# Dashboard.net
KiCad netlist of a schematic drawn in EAGLE
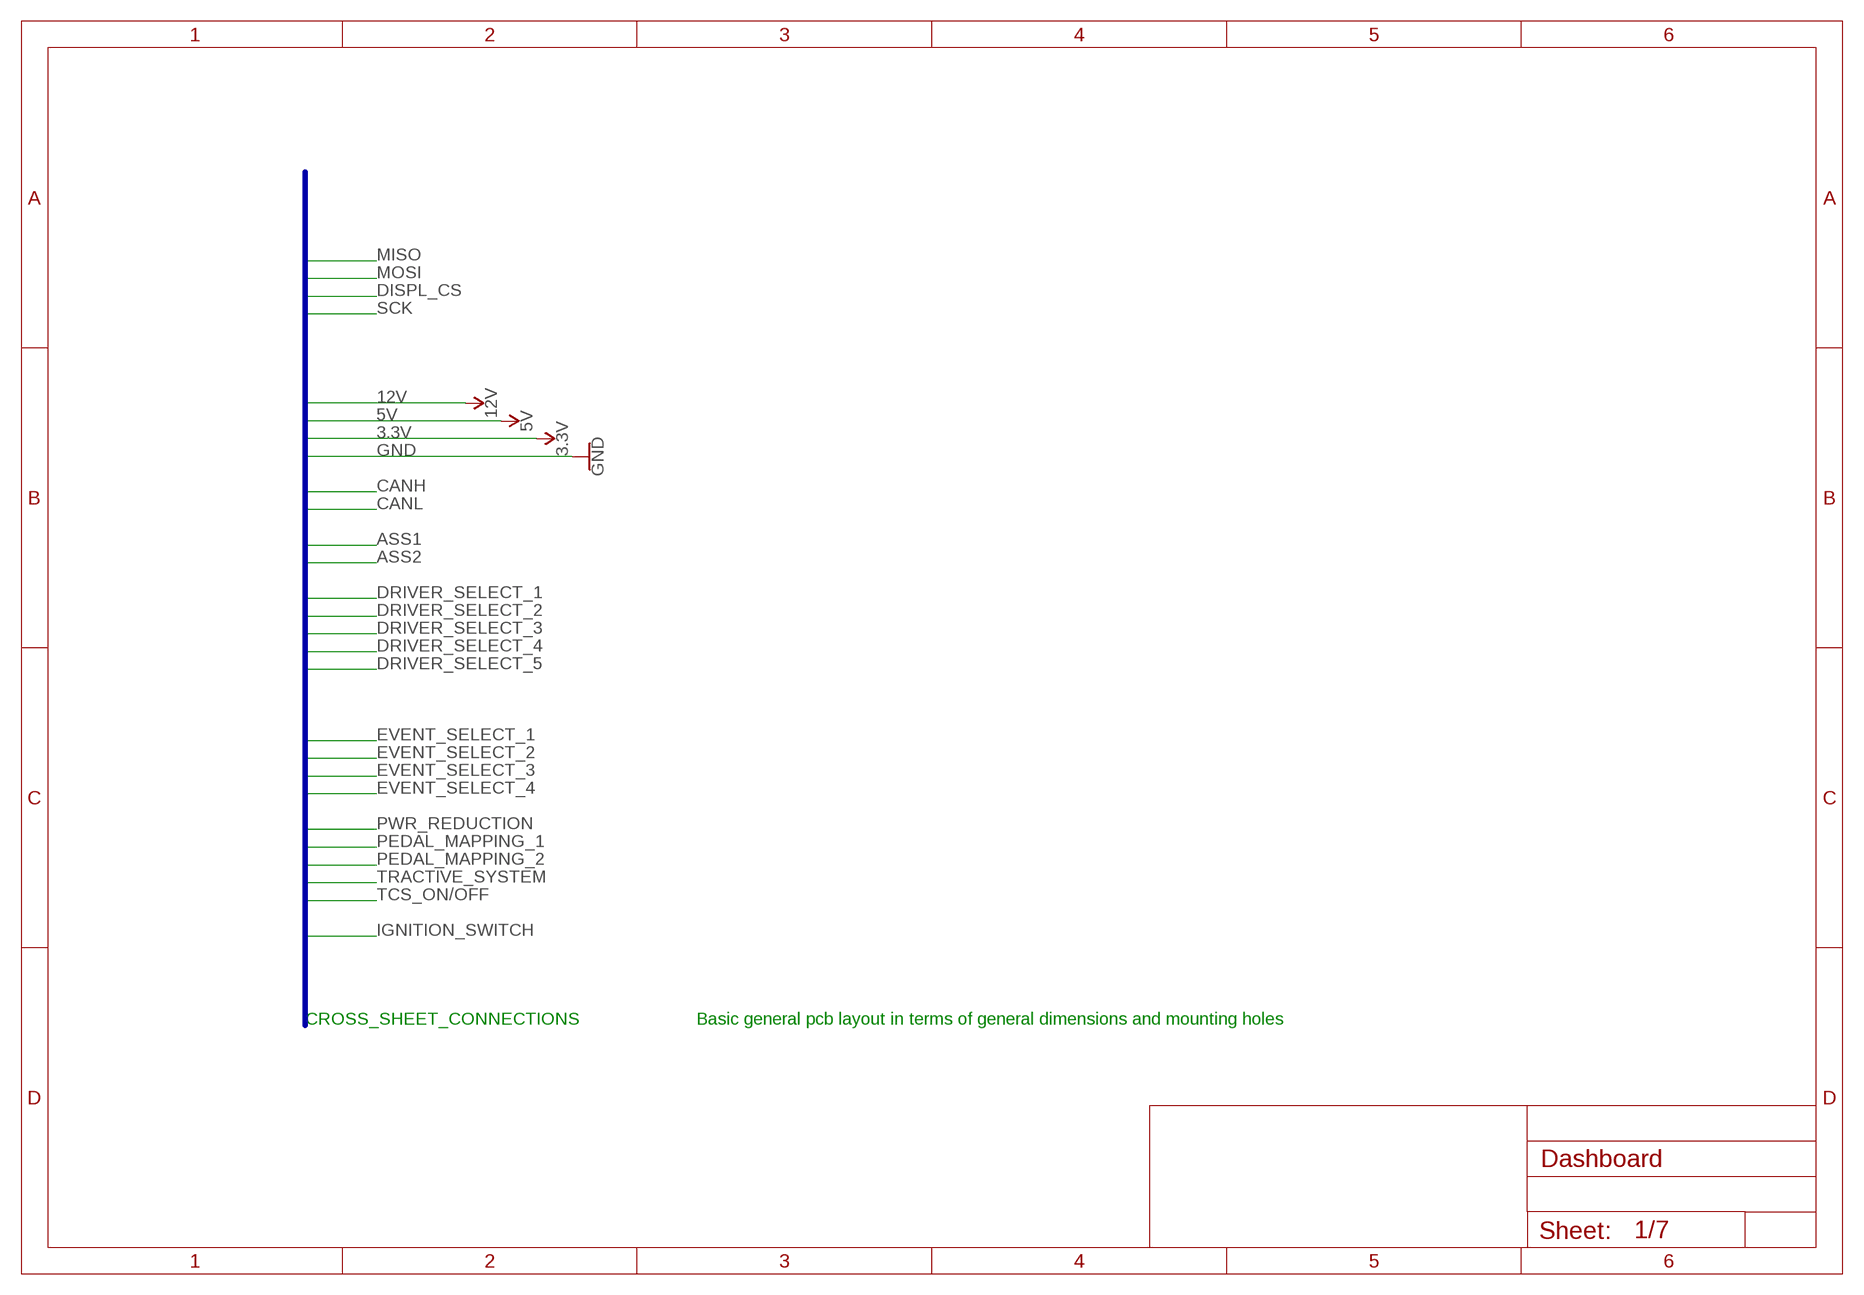
[diagram p0: schematic, sheet 1]
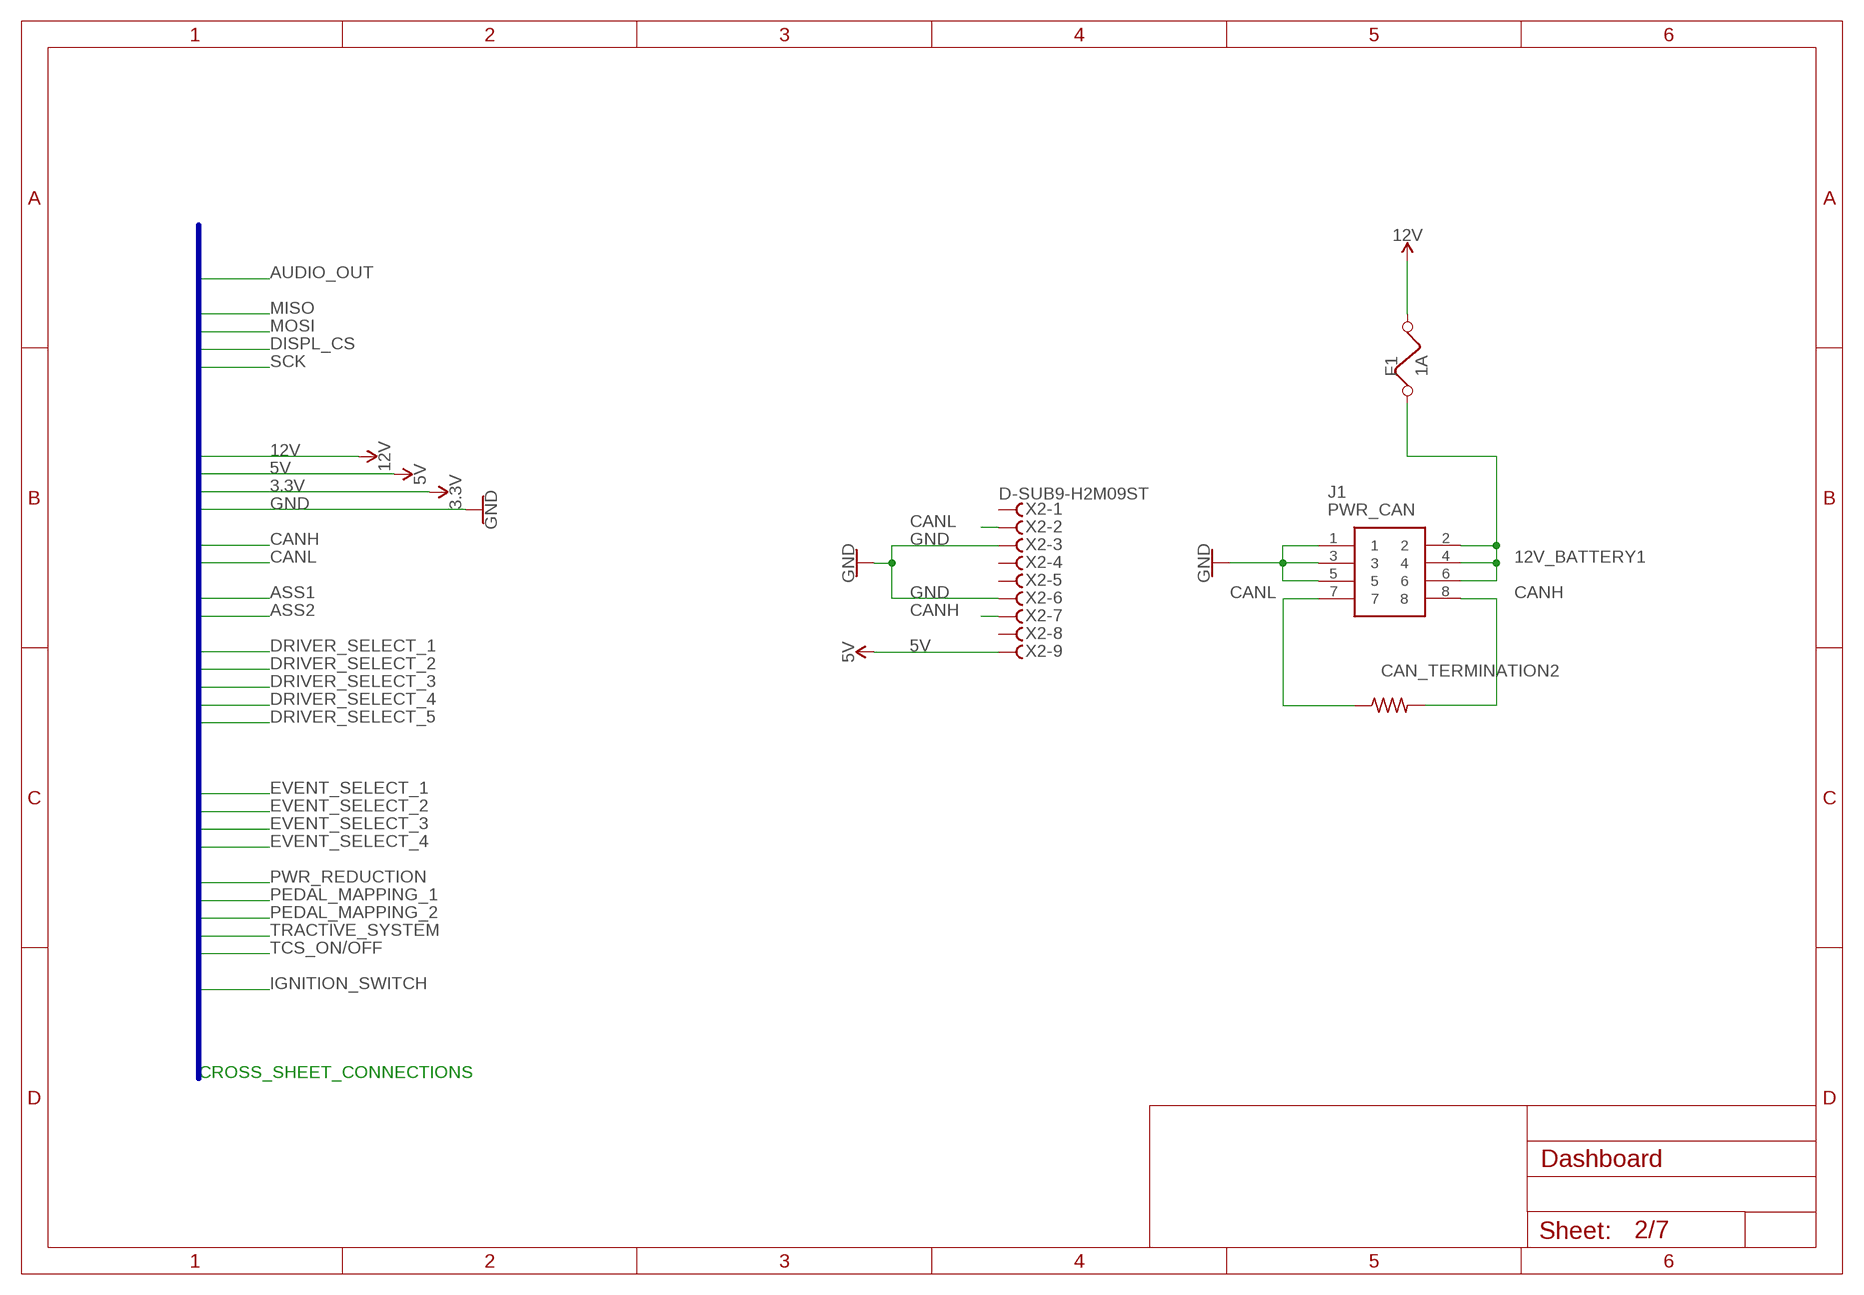
[diagram p1: schematic, sheet 2]
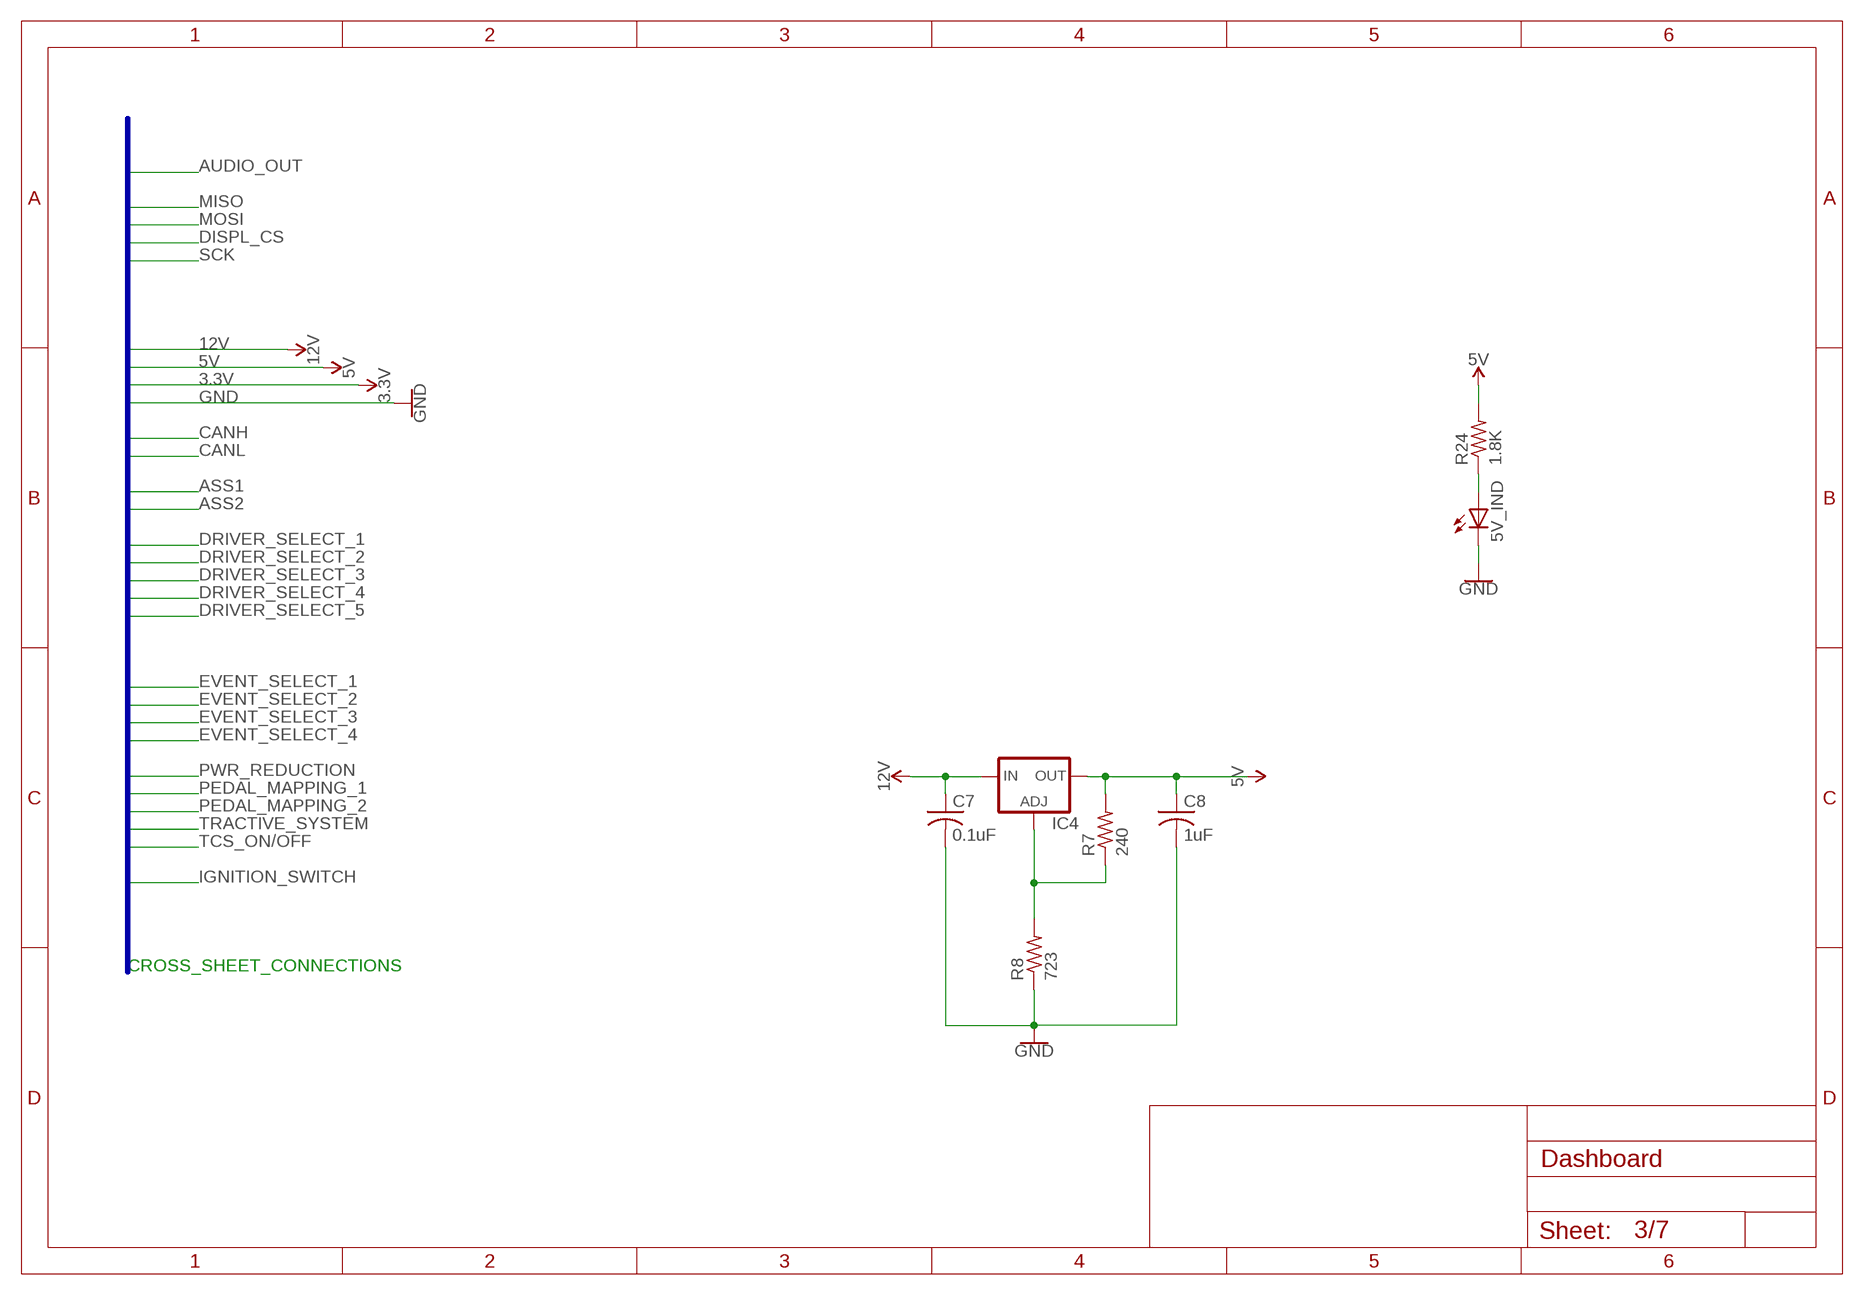
[diagram p2: schematic, sheet 3]
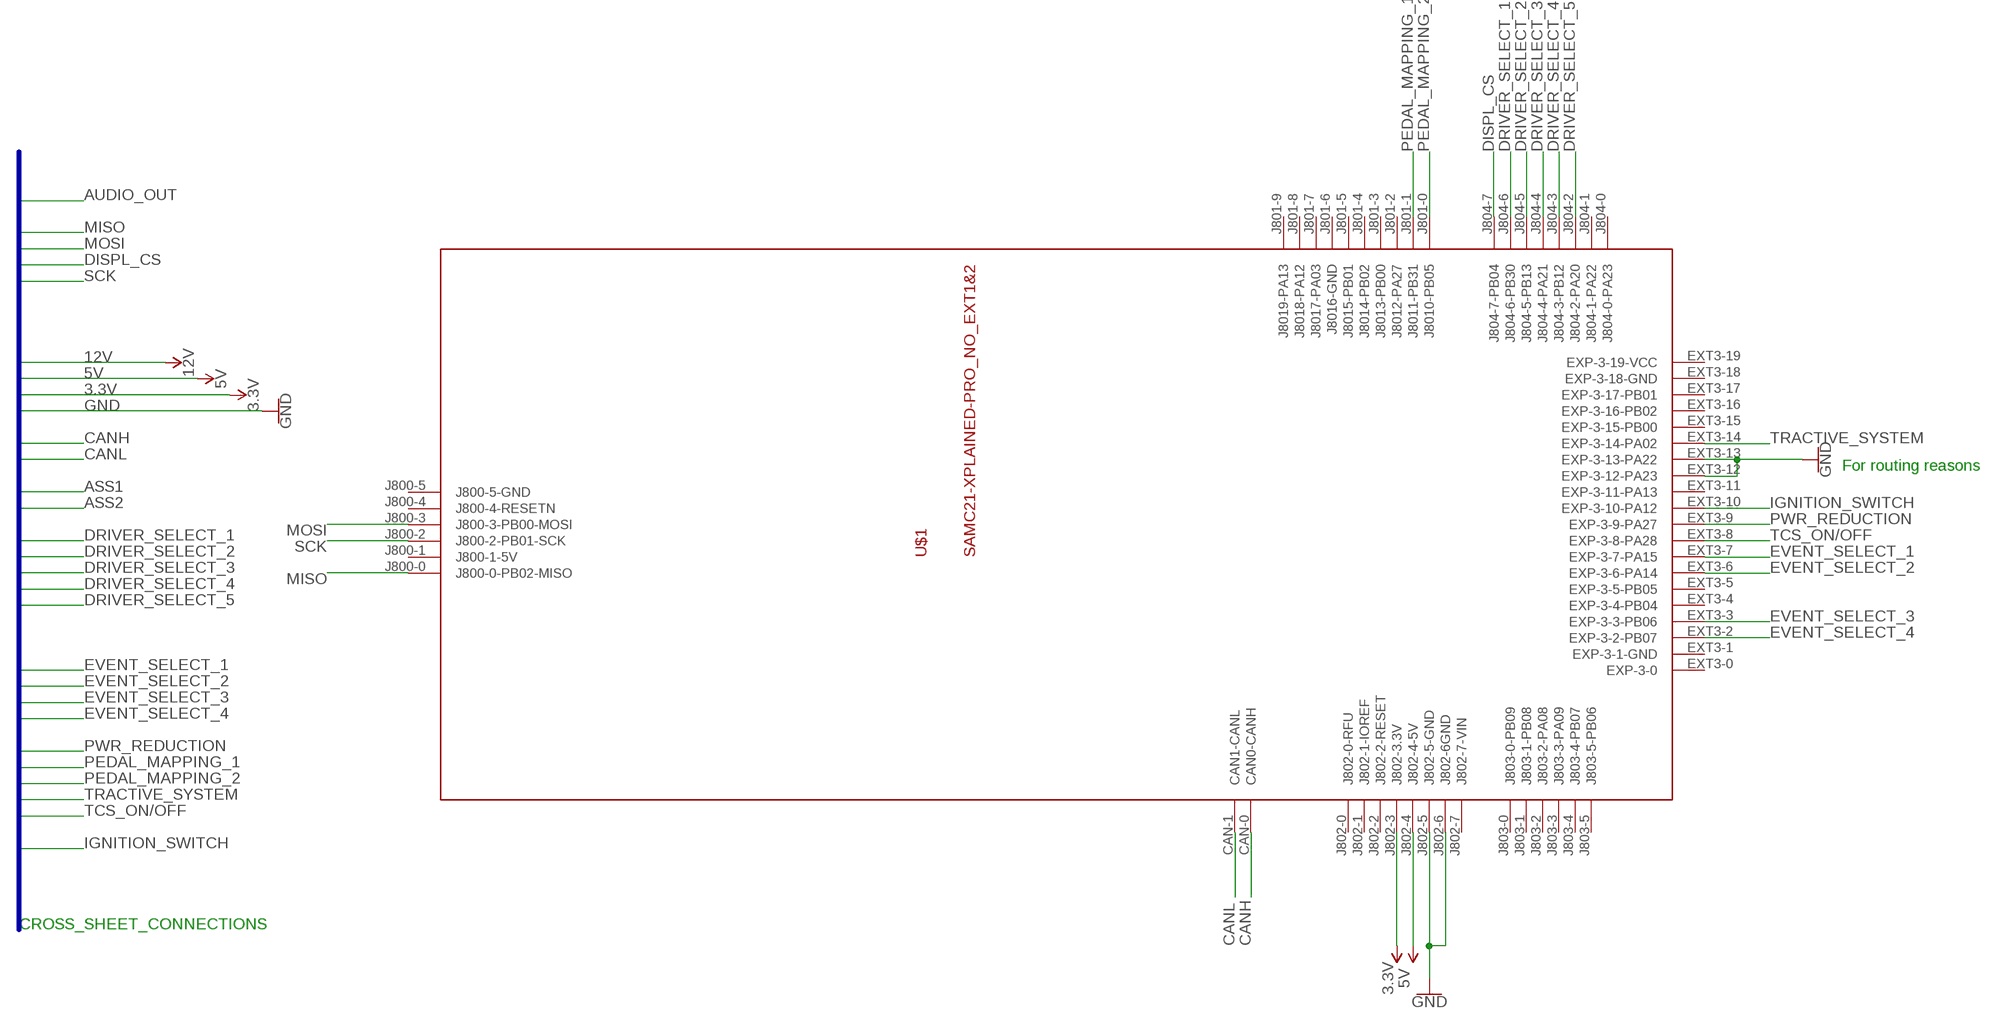
[diagram p3: schematic, sheet 4]
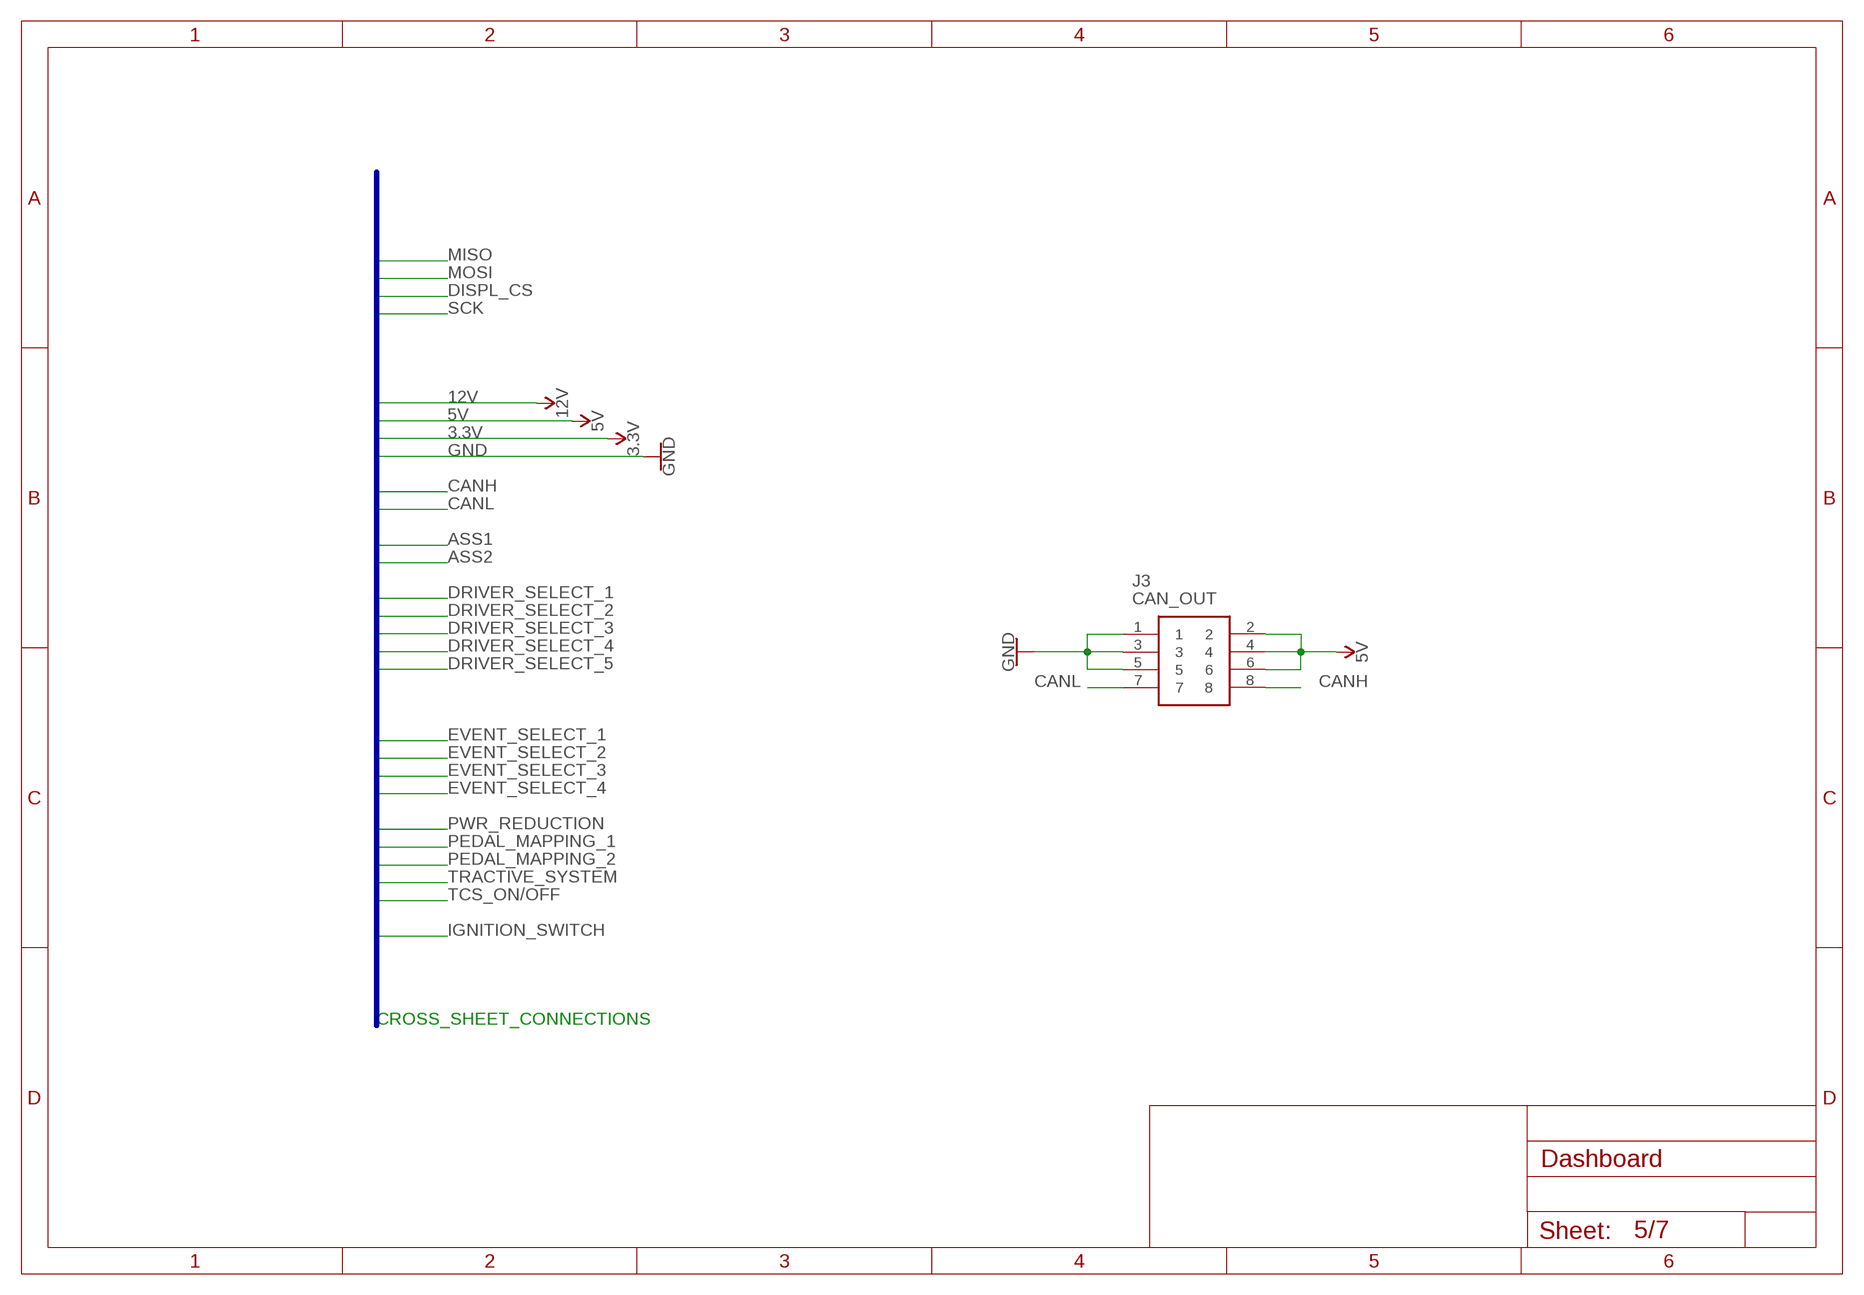
[diagram p4: schematic, sheet 5]
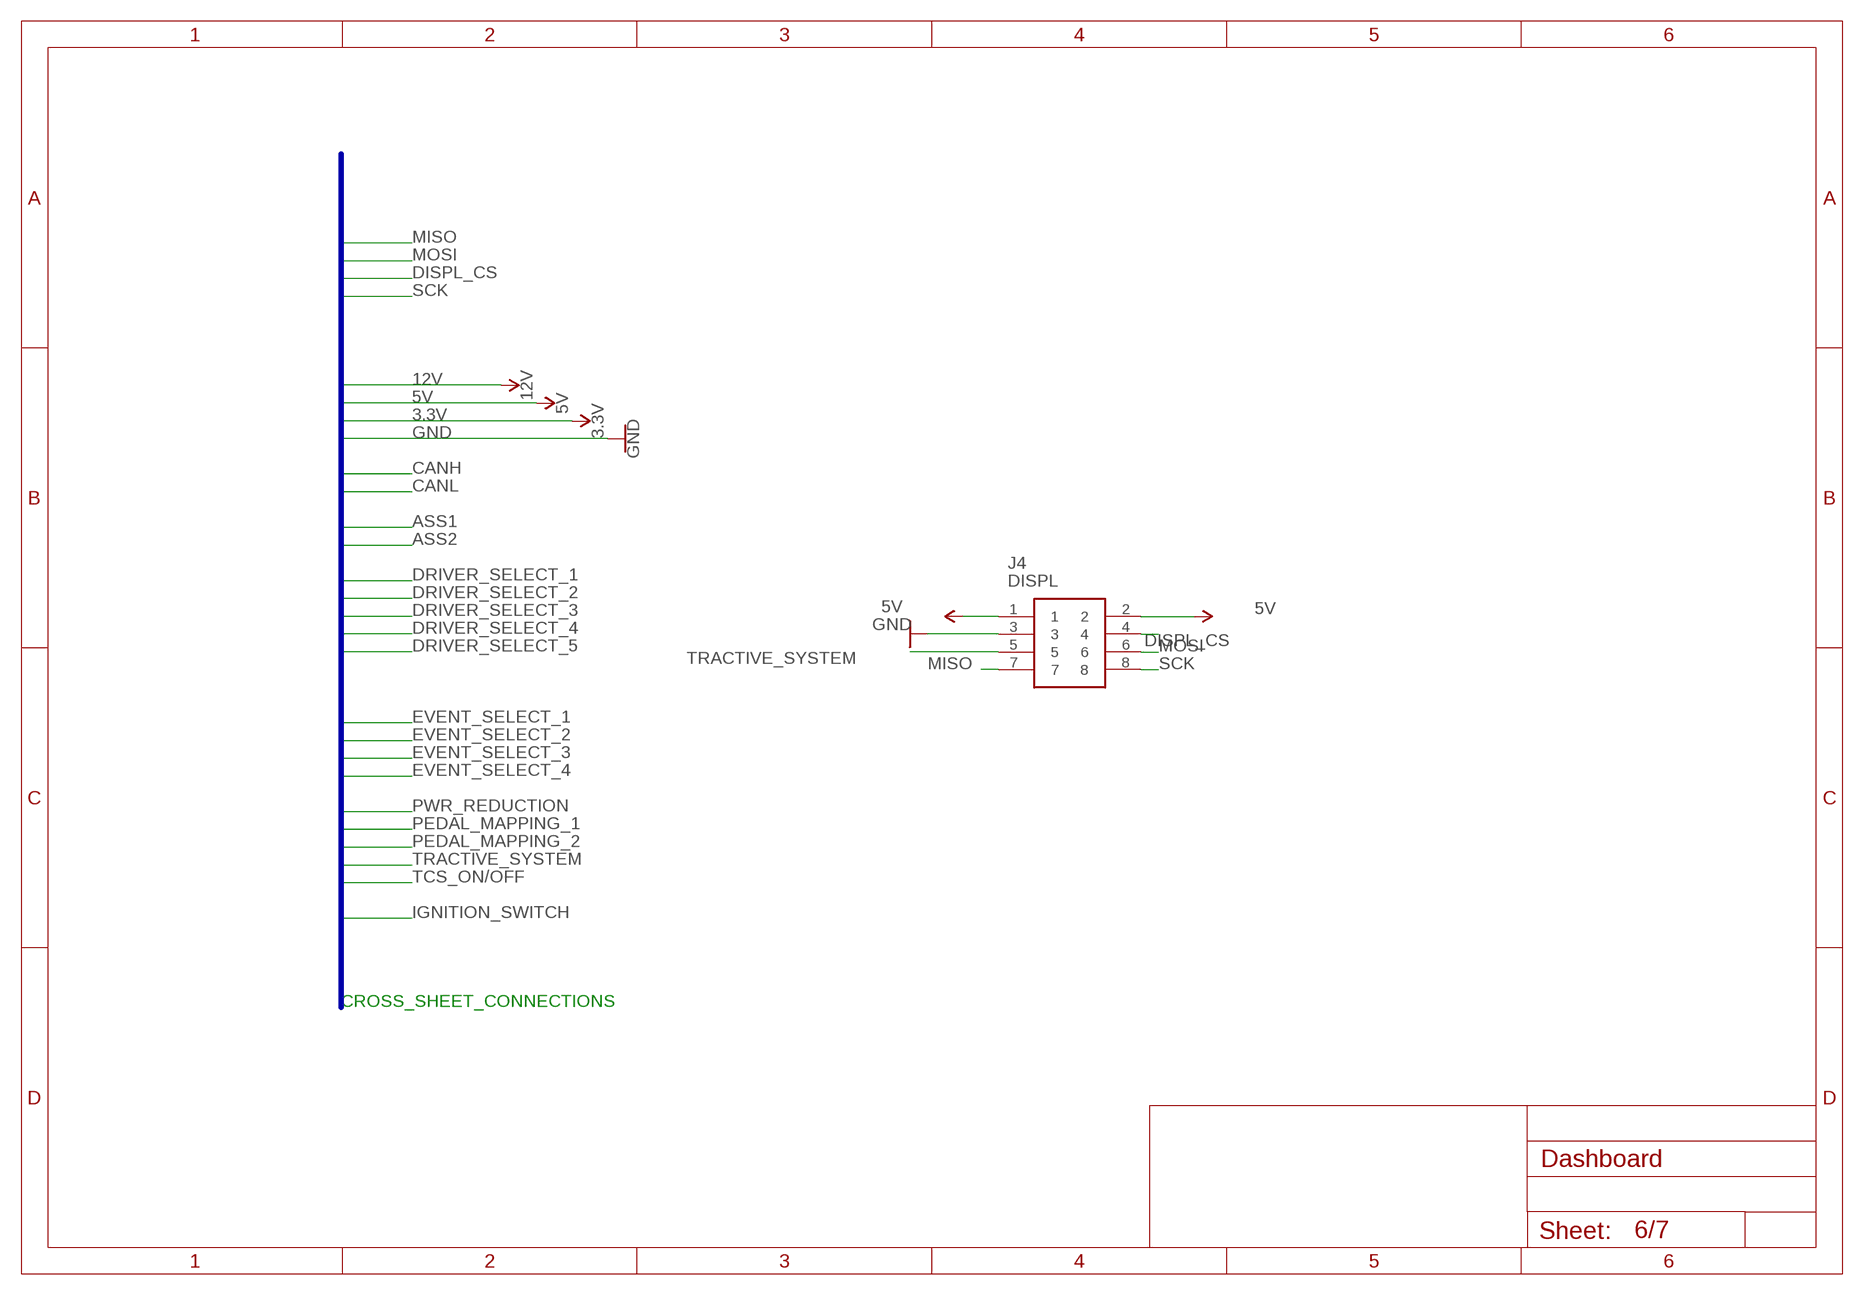
[diagram p5: schematic, sheet 6]
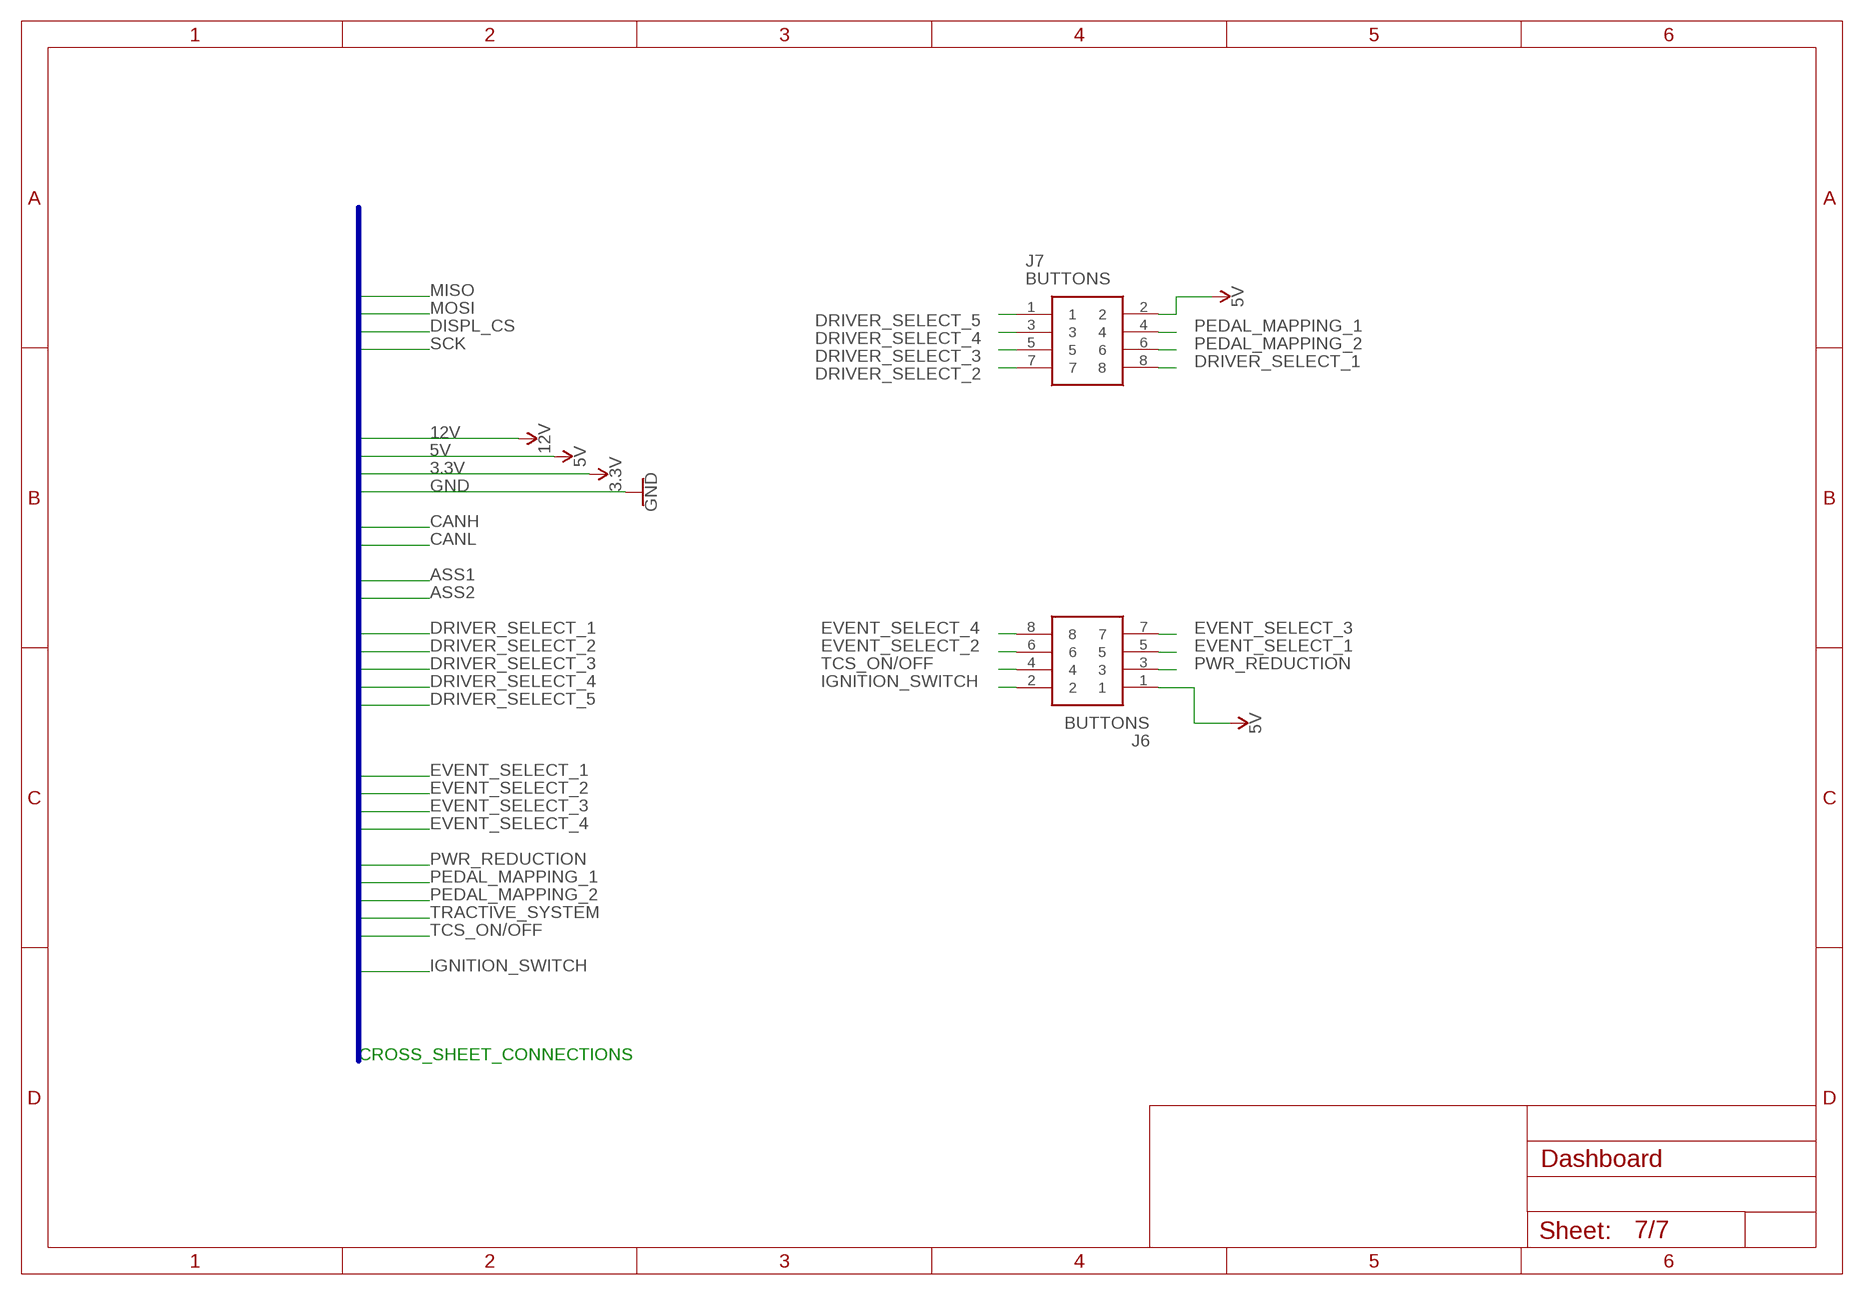
[diagram p6: schematic, sheet 7]

(export (version "E")
  (design (tool "Eeschema 10.0.6"))
  (components
    (comp (ref "J6")
      (value "BUTTONS")
      (footprint "eagle-import:HDRV8W64P254_2X4_1778X895X915P")
      (fields
        (field (name "MANUFACTURER_PART_NUMBER") "T821108A1S100CEU")
        (field (name "RS_PART_NUMBER") "1702738")
      )
      (libsource (lib "eagle-import") (part "T821108A1S100CEU"))
    )
    (comp (ref "J7")
      (value "BUTTONS")
      (footprint "eagle-import:HDRV8W64P254_2X4_1778X895X915P")
      (fields
        (field (name "MANUFACTURER_PART_NUMBER") "T821108A1S100CEU")
        (field (name "RS_PART_NUMBER") "1702738")
      )
      (libsource (lib "eagle-import") (part "T821108A1S100CEU"))
    )
    (comp (ref "J3")
      (value "CAN_OUT")
      (footprint "eagle-import:HDRV8W64P254_2X4_1778X895X915P")
      (fields
        (field (name "MANUFACTURER_PART_NUMBER") "T821108A1S100CEU")
        (field (name "RS_PART_NUMBER") "1702738")
      )
      (libsource (lib "eagle-import") (part "T821108A1S100CEU"))
    )
    (comp (ref "J4")
      (value "DISPL")
      (footprint "eagle-import:HDRV8W64P254_2X4_1778X895X915P")
      (fields
        (field (name "MANUFACTURER_PART_NUMBER") "T821108A1S100CEU")
        (field (name "RS_PART_NUMBER") "1702738")
      )
      (libsource (lib "eagle-import") (part "T821108A1S100CEU"))
    )
    (comp (ref "CAN_TERMINATION2")
      (value "120")
      (footprint "eagle-import:R0805")
      (libsource (lib "eagle-import") (part "R-US_R0805"))
    )
    (comp (ref "F1")
      (value "1A")
      (footprint "eagle-import:FUSE")
      (libsource (lib "eagle-import") (part "FUSE"))
    )
    (comp (ref "J1")
      (value "PWR_CAN")
      (footprint "eagle-import:HDRV8W64P254_2X4_1778X895X915P")
      (fields
        (field (name "MANUFACTURER_PART_NUMBER") "T821108A1S100CEU")
        (field (name "RS_PART_NUMBER") "1702738")
      )
      (libsource (lib "eagle-import") (part "T821108A1S100CEU"))
    )
    (comp (ref "X2")
      (value "D-SUB9-H2M09ST")
      (footprint "eagle-import:H2M09ST")
      (libsource (lib "eagle-import") (part "D-SUB9-H2M09ST"))
    )
    (comp (ref "5V_IND")
      (value "LED3MM")
      (footprint "eagle-import:LED3MM")
      (libsource (lib "eagle-import") (part "LED3MM"))
    )
    (comp (ref "C7")
      (value "0.1uF")
      (footprint "eagle-import:C050-025X075")
      (libsource (lib "eagle-import") (part "C-US050-025X075"))
    )
    (comp (ref "C8")
      (value "1uF")
      (footprint "eagle-import:C050-025X075")
      (libsource (lib "eagle-import") (part "C-US050-025X075"))
    )
    (comp (ref "IC4")
      (value "LM317TS")
      (footprint "eagle-import:317TS")
      (libsource (lib "eagle-import") (part "LM317TS"))
    )
    (comp (ref "R7")
      (value "240")
      (footprint "eagle-import:R0805")
      (libsource (lib "eagle-import") (part "R-US_R0805"))
    )
    (comp (ref "R8")
      (value "723")
      (footprint "eagle-import:R0805")
      (libsource (lib "eagle-import") (part "R-US_R0805"))
    )
    (comp (ref "R24")
      (value "1.8K")
      (footprint "eagle-import:R0805")
      (libsource (lib "eagle-import") (part "R-US_R0805"))
    )
    (comp (ref "U$1")
      (value "SAMC21-XPLAINED-PRO_NO_EXT1&2")
      (footprint "eagle-import:SAMC21-XPLAINED-PRO_NO_EXT1&2")
      (libsource (lib "eagle-import") (part "SAMC21-XPLAINED-PRO_NO_EXT1&2"))
    )
  )
  (nets
    (net (code "1") (name "3.3V") (class "Default")
      (node (ref "U$1") (pin "J802-3") (pinfunction "J802-3.3V_J802-3") (pintype "bidirectional"))
    )
    (net (code "2") (name "5V") (class "Default")
      (node (ref "C8") (pin "1") (pinfunction "1_1") (pintype "passive"))
      (node (ref "IC4") (pin "2") (pinfunction "OUT_2") (pintype "passive"))
      (node (ref "J3") (pin "2") (pinfunction "2_2") (pintype "bidirectional"))
      (node (ref "J3") (pin "4") (pinfunction "4_4") (pintype "bidirectional"))
      (node (ref "J3") (pin "6") (pinfunction "6_6") (pintype "bidirectional"))
      (node (ref "J4") (pin "1") (pinfunction "1_1") (pintype "bidirectional"))
      (node (ref "J4") (pin "2") (pinfunction "2_2") (pintype "bidirectional"))
      (node (ref "J6") (pin "1") (pinfunction "1_1") (pintype "bidirectional"))
      (node (ref "J7") (pin "2") (pinfunction "2_2") (pintype "bidirectional"))
      (node (ref "R24") (pin "2") (pinfunction "2_2") (pintype "passive"))
      (node (ref "R7") (pin "2") (pinfunction "2_2") (pintype "passive"))
      (node (ref "U$1") (pin "J802-4") (pinfunction "J802-4-5V_J802-4") (pintype "bidirectional"))
      (node (ref "X2") (pin "9") (pinfunction "F_9") (pintype "passive"))
    )
    (net (code "3") (name "12V") (class "Default")
      (node (ref "C7") (pin "1") (pinfunction "1_1") (pintype "passive"))
      (node (ref "F1") (pin "2") (pinfunction "2_2") (pintype "passive"))
      (node (ref "IC4") (pin "3") (pinfunction "IN_3") (pintype "input"))
    )
    (net (code "4") (name "12V_BATTERY1") (class "Default")
      (node (ref "F1") (pin "1") (pinfunction "1_1") (pintype "passive"))
      (node (ref "J1") (pin "2") (pinfunction "2_2") (pintype "bidirectional"))
      (node (ref "J1") (pin "4") (pinfunction "4_4") (pintype "bidirectional"))
      (node (ref "J1") (pin "6") (pinfunction "6_6") (pintype "bidirectional"))
    )
    (net (code "8") (name "CANH") (class "Default")
      (node (ref "CAN_TERMINATION2") (pin "2") (pinfunction "2_2") (pintype "passive"))
      (node (ref "J1") (pin "8") (pinfunction "8_8") (pintype "bidirectional"))
      (node (ref "J3") (pin "8") (pinfunction "8_8") (pintype "bidirectional"))
      (node (ref "U$1") (pin "CAN-0") (pinfunction "CAN0-CANH_CAN-0") (pintype "bidirectional"))
      (node (ref "X2") (pin "7") (pinfunction "F_7") (pintype "passive"))
    )
    (net (code "9") (name "CANL") (class "Default")
      (node (ref "CAN_TERMINATION2") (pin "1") (pinfunction "1_1") (pintype "passive"))
      (node (ref "J1") (pin "7") (pinfunction "7_7") (pintype "bidirectional"))
      (node (ref "J3") (pin "7") (pinfunction "7_7") (pintype "bidirectional"))
      (node (ref "U$1") (pin "CAN-1") (pinfunction "CAN1-CANL_CAN-1") (pintype "bidirectional"))
      (node (ref "X2") (pin "2") (pinfunction "F_2") (pintype "passive"))
    )
    (net (code "10") (name "DISPL_CS") (class "Default")
      (node (ref "J4") (pin "4") (pinfunction "4_4") (pintype "bidirectional"))
      (node (ref "U$1") (pin "J804-7") (pinfunction "J804-7-PB04_J804-7") (pintype "bidirectional"))
    )
    (net (code "11") (name "DRIVER_SELECT_1") (class "Default")
      (node (ref "J7") (pin "8") (pinfunction "8_8") (pintype "bidirectional"))
      (node (ref "U$1") (pin "J804-6") (pinfunction "J804-6-PB30_J804-6") (pintype "bidirectional"))
    )
    (net (code "12") (name "DRIVER_SELECT_2") (class "Default")
      (node (ref "J7") (pin "7") (pinfunction "7_7") (pintype "bidirectional"))
      (node (ref "U$1") (pin "J804-5") (pinfunction "J804-5-PB13_J804-5") (pintype "bidirectional"))
    )
    (net (code "13") (name "DRIVER_SELECT_3") (class "Default")
      (node (ref "J7") (pin "5") (pinfunction "5_5") (pintype "bidirectional"))
      (node (ref "U$1") (pin "J804-4") (pinfunction "J804-4-PA21_J804-4") (pintype "bidirectional"))
    )
    (net (code "14") (name "DRIVER_SELECT_4") (class "Default")
      (node (ref "J7") (pin "3") (pinfunction "3_3") (pintype "bidirectional"))
      (node (ref "U$1") (pin "J804-3") (pinfunction "J804-3-PB12_J804-3") (pintype "bidirectional"))
    )
    (net (code "15") (name "DRIVER_SELECT_5") (class "Default")
      (node (ref "J7") (pin "1") (pinfunction "1_1") (pintype "bidirectional"))
      (node (ref "U$1") (pin "J804-2") (pinfunction "J804-2-PA20_J804-2") (pintype "bidirectional"))
    )
    (net (code "16") (name "EVENT_SELECT_1") (class "Default")
      (node (ref "J6") (pin "5") (pinfunction "5_5") (pintype "bidirectional"))
      (node (ref "U$1") (pin "EXT3-7") (pinfunction "EXP-3-7-PA15_EXT3-7") (pintype "bidirectional"))
    )
    (net (code "17") (name "EVENT_SELECT_2") (class "Default")
      (node (ref "J6") (pin "6") (pinfunction "6_6") (pintype "bidirectional"))
      (node (ref "U$1") (pin "EXT3-6") (pinfunction "EXP-3-6-PA14_EXT3-6") (pintype "bidirectional"))
    )
    (net (code "18") (name "EVENT_SELECT_3") (class "Default")
      (node (ref "J6") (pin "7") (pinfunction "7_7") (pintype "bidirectional"))
      (node (ref "U$1") (pin "EXT3-3") (pinfunction "EXP-3-3-PB06_EXT3-3") (pintype "bidirectional"))
    )
    (net (code "19") (name "EVENT_SELECT_4") (class "Default")
      (node (ref "J6") (pin "8") (pinfunction "8_8") (pintype "bidirectional"))
      (node (ref "U$1") (pin "EXT3-2") (pinfunction "EXP-3-2-PB07_EXT3-2") (pintype "bidirectional"))
    )
    (net (code "20") (name "GND") (class "Default")
      (node (ref "5V_IND") (pin "K") (pinfunction "C_K") (pintype "passive"))
      (node (ref "C7") (pin "2") (pinfunction "2_2") (pintype "passive"))
      (node (ref "C8") (pin "2") (pinfunction "2_2") (pintype "passive"))
      (node (ref "J1") (pin "1") (pinfunction "1_1") (pintype "bidirectional"))
      (node (ref "J1") (pin "3") (pinfunction "3_3") (pintype "bidirectional"))
      (node (ref "J1") (pin "5") (pinfunction "5_5") (pintype "bidirectional"))
      (node (ref "J3") (pin "1") (pinfunction "1_1") (pintype "bidirectional"))
      (node (ref "J3") (pin "3") (pinfunction "3_3") (pintype "bidirectional"))
      (node (ref "J3") (pin "5") (pinfunction "5_5") (pintype "bidirectional"))
      (node (ref "J4") (pin "3") (pinfunction "3_3") (pintype "bidirectional"))
      (node (ref "R8") (pin "1") (pinfunction "1_1") (pintype "passive"))
      (node (ref "U$1") (pin "EXT3-12") (pinfunction "EXP-3-12-PA23_EXT3-12") (pintype "bidirectional"))
      (node (ref "U$1") (pin "EXT3-13") (pinfunction "EXP-3-13-PA22_EXT3-13") (pintype "bidirectional"))
      (node (ref "U$1") (pin "J802-5") (pinfunction "J802-5-GND_J802-5") (pintype "bidirectional"))
      (node (ref "U$1") (pin "J802-6") (pinfunction "J802-6GND_J802-6") (pintype "bidirectional"))
      (node (ref "X2") (pin "3") (pinfunction "F_3") (pintype "passive"))
      (node (ref "X2") (pin "6") (pinfunction "F_6") (pintype "passive"))
    )
    (net (code "21") (name "IGNITION_SWITCH") (class "Default")
      (node (ref "J6") (pin "2") (pinfunction "2_2") (pintype "bidirectional"))
      (node (ref "U$1") (pin "EXT3-10") (pinfunction "EXP-3-10-PA12_EXT3-10") (pintype "bidirectional"))
    )
    (net (code "22") (name "MISO") (class "Default")
      (node (ref "J4") (pin "7") (pinfunction "7_7") (pintype "bidirectional"))
      (node (ref "U$1") (pin "J800-0") (pinfunction "J800-0-PB02-MISO_J800-0") (pintype "bidirectional"))
    )
    (net (code "23") (name "MOSI") (class "Default")
      (node (ref "J4") (pin "6") (pinfunction "6_6") (pintype "bidirectional"))
      (node (ref "U$1") (pin "J800-3") (pinfunction "J800-3-PB00-MOSI_J800-3") (pintype "bidirectional"))
    )
    (net (code "24") (name "Net-(5V_IND-PadA)") (class "Default")
      (node (ref "5V_IND") (pin "A") (pinfunction "A_A") (pintype "passive"))
      (node (ref "R24") (pin "1") (pinfunction "1_1") (pintype "passive"))
    )
    (net (code "25") (name "Net-(IC4-ADJ)") (class "Default")
      (node (ref "IC4") (pin "1") (pinfunction "ADJ_1") (pintype "input"))
      (node (ref "R7") (pin "1") (pinfunction "1_1") (pintype "passive"))
      (node (ref "R8") (pin "2") (pinfunction "2_2") (pintype "passive"))
    )
    (net (code "26") (name "PEDAL_MAPPING_1") (class "Default")
      (node (ref "J7") (pin "4") (pinfunction "4_4") (pintype "bidirectional"))
      (node (ref "U$1") (pin "J801-1") (pinfunction "J8011-PB31_J801-1") (pintype "bidirectional"))
    )
    (net (code "27") (name "PEDAL_MAPPING_2") (class "Default")
      (node (ref "J7") (pin "6") (pinfunction "6_6") (pintype "bidirectional"))
      (node (ref "U$1") (pin "J801-0") (pinfunction "J8010-PB05_J801-0") (pintype "bidirectional"))
    )
    (net (code "28") (name "PWR_REDUCTION") (class "Default")
      (node (ref "J6") (pin "3") (pinfunction "3_3") (pintype "bidirectional"))
      (node (ref "U$1") (pin "EXT3-9") (pinfunction "EXP-3-9-PA27_EXT3-9") (pintype "bidirectional"))
    )
    (net (code "29") (name "SCK") (class "Default")
      (node (ref "J4") (pin "8") (pinfunction "8_8") (pintype "bidirectional"))
      (node (ref "U$1") (pin "J800-2") (pinfunction "J800-2-PB01-SCK_J800-2") (pintype "bidirectional"))
    )
    (net (code "30") (name "TCS_ON{slash}OFF") (class "Default")
      (node (ref "J6") (pin "4") (pinfunction "4_4") (pintype "bidirectional"))
      (node (ref "U$1") (pin "EXT3-8") (pinfunction "EXP-3-8-PA28_EXT3-8") (pintype "bidirectional"))
    )
    (net (code "31") (name "TRACTIVE_SYSTEM") (class "Default")
      (node (ref "J4") (pin "5") (pinfunction "5_5") (pintype "bidirectional"))
      (node (ref "U$1") (pin "EXT3-14") (pinfunction "EXP-3-14-PA02_EXT3-14") (pintype "bidirectional"))
    )
    (net (code "32") (name "unconnected-(U$1-EXP-3-0-PadEXT3-0)") (class "Default")
      (node (ref "U$1") (pin "EXT3-0") (pinfunction "EXP-3-0_EXT3-0") (pintype "bidirectional"))
    )
    (net (code "33") (name "unconnected-(U$1-EXP-3-1-GND-PadEXT3-1)") (class "Default")
      (node (ref "U$1") (pin "EXT3-1") (pinfunction "EXP-3-1-GND_EXT3-1") (pintype "bidirectional"))
    )
    (net (code "34") (name "unconnected-(U$1-EXP-3-4-PB04-PadEXT3-4)") (class "Default")
      (node (ref "U$1") (pin "EXT3-4") (pinfunction "EXP-3-4-PB04_EXT3-4") (pintype "bidirectional"))
    )
    (net (code "35") (name "unconnected-(U$1-EXP-3-5-PB05-PadEXT3-5)") (class "Default")
      (node (ref "U$1") (pin "EXT3-5") (pinfunction "EXP-3-5-PB05_EXT3-5") (pintype "bidirectional"))
    )
    (net (code "36") (name "unconnected-(U$1-EXP-3-11-PA13-PadEXT3-11)") (class "Default")
      (node (ref "U$1") (pin "EXT3-11") (pinfunction "EXP-3-11-PA13_EXT3-11") (pintype "bidirectional"))
    )
    (net (code "37") (name "unconnected-(U$1-EXP-3-15-PB00-PadEXT3-15)") (class "Default")
      (node (ref "U$1") (pin "EXT3-15") (pinfunction "EXP-3-15-PB00_EXT3-15") (pintype "bidirectional"))
    )
    (net (code "38") (name "unconnected-(U$1-EXP-3-16-PB02-PadEXT3-16)") (class "Default")
      (node (ref "U$1") (pin "EXT3-16") (pinfunction "EXP-3-16-PB02_EXT3-16") (pintype "bidirectional"))
    )
    (net (code "39") (name "unconnected-(U$1-EXP-3-17-PB01-PadEXT3-17)") (class "Default")
      (node (ref "U$1") (pin "EXT3-17") (pinfunction "EXP-3-17-PB01_EXT3-17") (pintype "bidirectional"))
    )
    (net (code "40") (name "unconnected-(U$1-EXP-3-18-GND-PadEXT3-18)") (class "Default")
      (node (ref "U$1") (pin "EXT3-18") (pinfunction "EXP-3-18-GND_EXT3-18") (pintype "bidirectional"))
    )
    (net (code "41") (name "unconnected-(U$1-EXP-3-19-VCC-PadEXT3-19)") (class "Default")
      (node (ref "U$1") (pin "EXT3-19") (pinfunction "EXP-3-19-VCC_EXT3-19") (pintype "bidirectional"))
    )
    (net (code "42") (name "unconnected-(U$1-J800-1-5V-PadJ800-1)") (class "Default")
      (node (ref "U$1") (pin "J800-1") (pinfunction "J800-1-5V_J800-1") (pintype "bidirectional"))
    )
    (net (code "43") (name "unconnected-(U$1-J800-4-RESETN-PadJ800-4)") (class "Default")
      (node (ref "U$1") (pin "J800-4") (pinfunction "J800-4-RESETN_J800-4") (pintype "bidirectional"))
    )
    (net (code "44") (name "unconnected-(U$1-J800-5-GND-PadJ800-5)") (class "Default")
      (node (ref "U$1") (pin "J800-5") (pinfunction "J800-5-GND_J800-5") (pintype "bidirectional"))
    )
    (net (code "45") (name "unconnected-(U$1-J802-0-RFU-PadJ802-0)") (class "Default")
      (node (ref "U$1") (pin "J802-0") (pinfunction "J802-0-RFU_J802-0") (pintype "bidirectional"))
    )
    (net (code "46") (name "unconnected-(U$1-J802-1-IOREF-PadJ802-1)") (class "Default")
      (node (ref "U$1") (pin "J802-1") (pinfunction "J802-1-IOREF_J802-1") (pintype "bidirectional"))
    )
    (net (code "47") (name "unconnected-(U$1-J802-2-RESET-PadJ802-2)") (class "Default")
      (node (ref "U$1") (pin "J802-2") (pinfunction "J802-2-RESET_J802-2") (pintype "bidirectional"))
    )
    (net (code "48") (name "unconnected-(U$1-J802-7-VIN-PadJ802-7)") (class "Default")
      (node (ref "U$1") (pin "J802-7") (pinfunction "J802-7-VIN_J802-7") (pintype "bidirectional"))
    )
    (net (code "49") (name "unconnected-(U$1-J803-0-PB09-PadJ803-0)") (class "Default")
      (node (ref "U$1") (pin "J803-0") (pinfunction "J803-0-PB09_J803-0") (pintype "bidirectional"))
    )
    (net (code "50") (name "unconnected-(U$1-J803-1-PB08-PadJ803-1)") (class "Default")
      (node (ref "U$1") (pin "J803-1") (pinfunction "J803-1-PB08_J803-1") (pintype "bidirectional"))
    )
    (net (code "51") (name "unconnected-(U$1-J803-2-PA08-PadJ803-2)") (class "Default")
      (node (ref "U$1") (pin "J803-2") (pinfunction "J803-2-PA08_J803-2") (pintype "bidirectional"))
    )
    (net (code "52") (name "unconnected-(U$1-J803-3-PA09-PadJ803-3)") (class "Default")
      (node (ref "U$1") (pin "J803-3") (pinfunction "J803-3-PA09_J803-3") (pintype "bidirectional"))
    )
    (net (code "53") (name "unconnected-(U$1-J803-4-PB07-PadJ803-4)") (class "Default")
      (node (ref "U$1") (pin "J803-4") (pinfunction "J803-4-PB07_J803-4") (pintype "bidirectional"))
    )
    (net (code "54") (name "unconnected-(U$1-J803-5-PB06-PadJ803-5)") (class "Default")
      (node (ref "U$1") (pin "J803-5") (pinfunction "J803-5-PB06_J803-5") (pintype "bidirectional"))
    )
    (net (code "55") (name "unconnected-(U$1-J804-0-PA23-PadJ804-0)") (class "Default")
      (node (ref "U$1") (pin "J804-0") (pinfunction "J804-0-PA23_J804-0") (pintype "bidirectional"))
    )
    (net (code "56") (name "unconnected-(U$1-J804-1-PA22-PadJ804-1)") (class "Default")
      (node (ref "U$1") (pin "J804-1") (pinfunction "J804-1-PA22_J804-1") (pintype "bidirectional"))
    )
    (net (code "57") (name "unconnected-(U$1-J8012-PA27-PadJ801-2)") (class "Default")
      (node (ref "U$1") (pin "J801-2") (pinfunction "J8012-PA27_J801-2") (pintype "bidirectional"))
    )
    (net (code "58") (name "unconnected-(U$1-J8013-PB00-PadJ801-3)") (class "Default")
      (node (ref "U$1") (pin "J801-3") (pinfunction "J8013-PB00_J801-3") (pintype "bidirectional"))
    )
    (net (code "59") (name "unconnected-(U$1-J8014-PB02-PadJ801-4)") (class "Default")
      (node (ref "U$1") (pin "J801-4") (pinfunction "J8014-PB02_J801-4") (pintype "bidirectional"))
    )
    (net (code "60") (name "unconnected-(U$1-J8015-PB01-PadJ801-5)") (class "Default")
      (node (ref "U$1") (pin "J801-5") (pinfunction "J8015-PB01_J801-5") (pintype "bidirectional"))
    )
    (net (code "61") (name "unconnected-(U$1-J8016-GND-PadJ801-6)") (class "Default")
      (node (ref "U$1") (pin "J801-6") (pinfunction "J8016-GND_J801-6") (pintype "bidirectional"))
    )
    (net (code "62") (name "unconnected-(U$1-J8017-PA03-PadJ801-7)") (class "Default")
      (node (ref "U$1") (pin "J801-7") (pinfunction "J8017-PA03_J801-7") (pintype "bidirectional"))
    )
    (net (code "63") (name "unconnected-(U$1-J8018-PA12-PadJ801-8)") (class "Default")
      (node (ref "U$1") (pin "J801-8") (pinfunction "J8018-PA12_J801-8") (pintype "bidirectional"))
    )
    (net (code "64") (name "unconnected-(U$1-J8019-PA13-PadJ801-9)") (class "Default")
      (node (ref "U$1") (pin "J801-9") (pinfunction "J8019-PA13_J801-9") (pintype "bidirectional"))
    )
    (net (code "65") (name "unconnected-(X2A-F-Pad1)") (class "Default")
      (node (ref "X2") (pin "1") (pinfunction "F_1") (pintype "passive"))
    )
    (net (code "66") (name "unconnected-(X2D-F-Pad4)") (class "Default")
      (node (ref "X2") (pin "4") (pinfunction "F_4") (pintype "passive"))
    )
    (net (code "67") (name "unconnected-(X2E-F-Pad5)") (class "Default")
      (node (ref "X2") (pin "5") (pinfunction "F_5") (pintype "passive"))
    )
    (net (code "68") (name "unconnected-(X2H-F-Pad8)") (class "Default")
      (node (ref "X2") (pin "8") (pinfunction "F_8") (pintype "passive"))
    )
  )
)
